# T_STorM32_motor_v251E.net
KiCad netlist of a schematic drawn in EAGLE
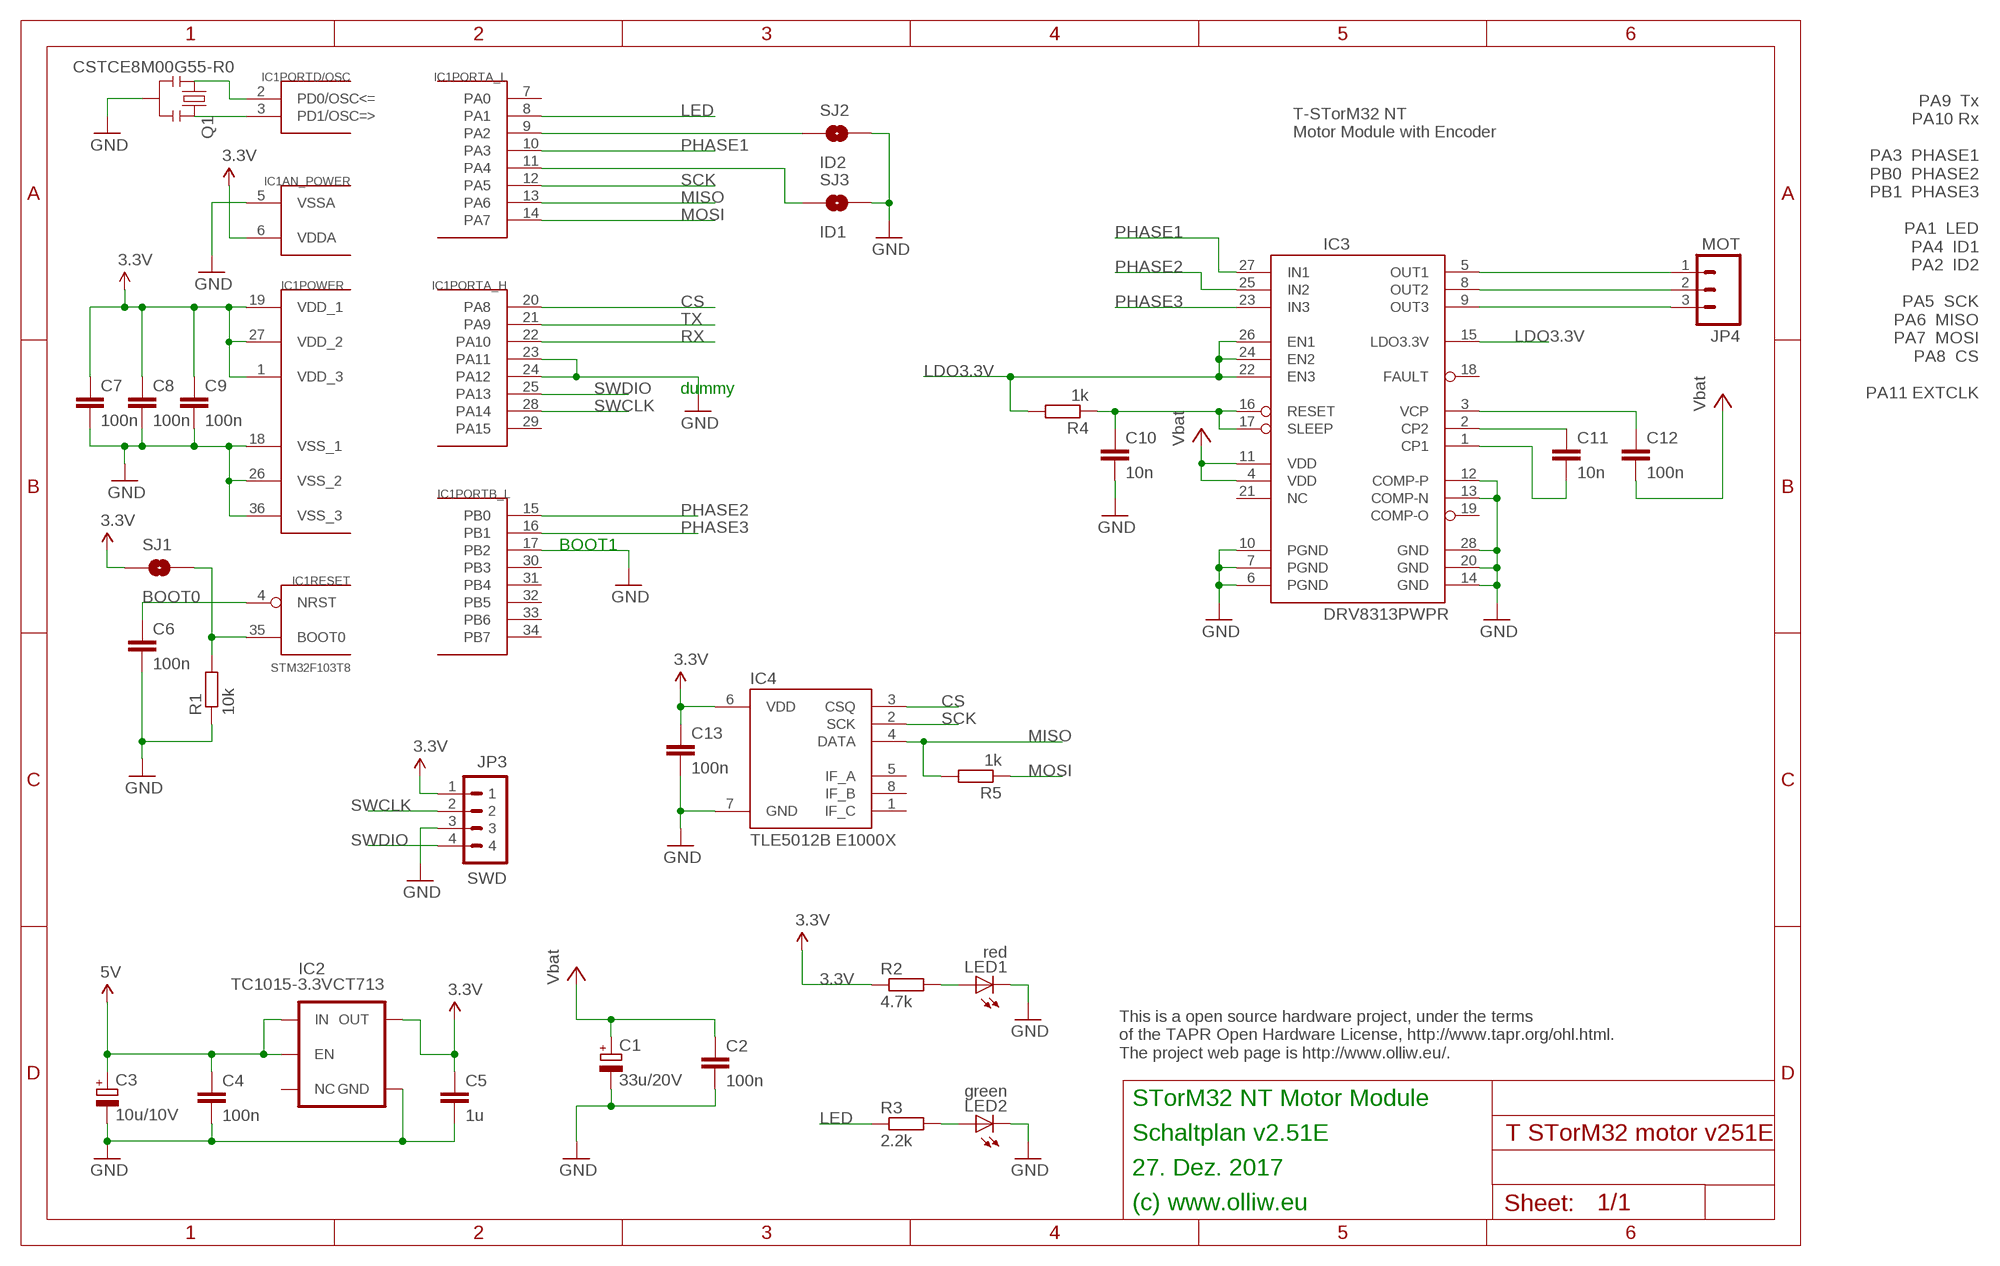
[diagram p0: schematic, sheet 1]

(export (version "E")
  (design (tool "Eeschema 10.0.6"))
  (components
    (comp (ref "C1")
      (value "33u/20V")
      (footprint "eagle-import:SMC_C")
      (libsource (lib "eagle-import") (part "CPOL-EUSMCC"))
    )
    (comp (ref "C2")
      (value "100n")
      (footprint "eagle-import:C0603")
      (libsource (lib "eagle-import") (part "C-EUC0603"))
    )
    (comp (ref "C3")
      (value "10u/10V")
      (footprint "eagle-import:SMC_B")
      (libsource (lib "eagle-import") (part "CPOL-EUSMCB"))
    )
    (comp (ref "C4")
      (value "100n")
      (footprint "eagle-import:C0603")
      (libsource (lib "eagle-import") (part "C-EUC0603"))
    )
    (comp (ref "C5")
      (value "1u")
      (footprint "eagle-import:C0603")
      (libsource (lib "eagle-import") (part "C-EUC0603"))
    )
    (comp (ref "C6")
      (value "100n")
      (footprint "eagle-import:C0603")
      (libsource (lib "eagle-import") (part "C-EUC0603"))
    )
    (comp (ref "C7")
      (value "100n")
      (footprint "eagle-import:C0603")
      (libsource (lib "eagle-import") (part "C-EUC0603"))
    )
    (comp (ref "C8")
      (value "100n")
      (footprint "eagle-import:C0603")
      (libsource (lib "eagle-import") (part "C-EUC0603"))
    )
    (comp (ref "C9")
      (value "100n")
      (footprint "eagle-import:C0603")
      (libsource (lib "eagle-import") (part "C-EUC0603"))
    )
    (comp (ref "C10")
      (value "10n")
      (footprint "eagle-import:C0603")
      (libsource (lib "eagle-import") (part "C-EUC0603"))
    )
    (comp (ref "C11")
      (value "10n")
      (footprint "eagle-import:C0603")
      (libsource (lib "eagle-import") (part "C-EUC0603"))
    )
    (comp (ref "C12")
      (value "100n")
      (footprint "eagle-import:C0603")
      (libsource (lib "eagle-import") (part "C-EUC0603"))
    )
    (comp (ref "C13")
      (value "100n")
      (footprint "eagle-import:C0603")
      (libsource (lib "eagle-import") (part "C-EUC0603"))
    )
    (comp (ref "IC1")
      (value "STM32F103T8")
      (footprint "eagle-import:VFQFPN36")
      (libsource (lib "eagle-import") (part "STM32F10XTXU6"))
    )
    (comp (ref "IC2")
      (value "TC1015-3.3VCT713")
      (footprint "eagle-import:SOT23-5")
      (libsource (lib "eagle-import") (part "V_REG_TPS76433SOT23-5"))
    )
    (comp (ref "IC3")
      (value "DRV8313PWPR")
      (footprint "eagle-import:HTSSOP28")
      (libsource (lib "eagle-import") (part "DRV8313"))
    )
    (comp (ref "IC4")
      (value "TLE5012B E1000X")
      (footprint "eagle-import:SO08")
      (libsource (lib "eagle-import") (part "TLE5012B"))
    )
    (comp (ref "JP3")
      (value "SWD")
      (footprint "eagle-import:4X1_1P27_OCT_BILEX")
      (libsource (lib "eagle-import") (part "P4X1_1P27-OCT_BILEX"))
    )
    (comp (ref "JP4")
      (value "MOT")
      (footprint "eagle-import:1X03_NO_SILK")
      (libsource (lib "eagle-import") (part "M031X03_NO_SILK"))
    )
    (comp (ref "LED1")
      (value "red")
      (footprint "eagle-import:CHIPLED_0603")
      (libsource (lib "eagle-import") (part "LEDCHIPLED_0603"))
    )
    (comp (ref "LED2")
      (value "green")
      (footprint "eagle-import:CHIPLED_0603")
      (libsource (lib "eagle-import") (part "LEDCHIPLED_0603"))
    )
    (comp (ref "Q1")
      (value "CSTCE8M00G55-R0")
      (footprint "eagle-import:RESONATOR-SMD")
      (libsource (lib "eagle-import") (part "RESONATORSMD"))
    )
    (comp (ref "R1")
      (value "10k")
      (footprint "eagle-import:R0603")
      (libsource (lib "eagle-import") (part "R-EU_R0603"))
    )
    (comp (ref "R2")
      (value "4.7k")
      (footprint "eagle-import:R0603")
      (libsource (lib "eagle-import") (part "R-EU_R0603"))
    )
    (comp (ref "R3")
      (value "2.2k")
      (footprint "eagle-import:R0603")
      (libsource (lib "eagle-import") (part "R-EU_R0603"))
    )
    (comp (ref "R4")
      (value "1k")
      (footprint "eagle-import:R0603")
      (libsource (lib "eagle-import") (part "R-EU_R0603"))
    )
    (comp (ref "R5")
      (value "1k")
      (footprint "eagle-import:R0603")
      (libsource (lib "eagle-import") (part "R-EU_R0603"))
    )
    (comp (ref "SJ1")
      (value "BOOT0")
      (footprint "eagle-import:SJ_2S-NO")
      (libsource (lib "eagle-import") (part "SOLDERJUMPERNO"))
    )
    (comp (ref "SJ2")
      (value "ID2")
      (footprint "eagle-import:SJ_2S-NO")
      (libsource (lib "eagle-import") (part "SOLDERJUMPERNO"))
    )
    (comp (ref "SJ3")
      (value "ID1")
      (footprint "eagle-import:SJ_2S-NO")
      (libsource (lib "eagle-import") (part "SOLDERJUMPERNO"))
    )
  )
  (nets
    (net (code "1") (name "/CS") (class "Default")
      (node (ref "IC1") (pin "20") (pinfunction "PA8_20") (pintype "bidirectional"))
      (node (ref "IC4") (pin "3") (pinfunction "CSQ_3") (pintype "input"))
    )
    (net (code "2") (name "/LDO3.3V") (class "Default")
      (node (ref "IC3") (pin "15") (pinfunction "LDO3.3V_15") (pintype "output"))
      (node (ref "IC3") (pin "22") (pinfunction "EN3_22") (pintype "input"))
      (node (ref "IC3") (pin "24") (pinfunction "EN2_24") (pintype "input"))
      (node (ref "IC3") (pin "26") (pinfunction "EN1_26") (pintype "input"))
      (node (ref "R4") (pin "2") (pinfunction "2_2") (pintype "passive"))
    )
    (net (code "3") (name "/LED") (class "Default")
      (node (ref "IC1") (pin "8") (pinfunction "PA1_8") (pintype "bidirectional"))
      (node (ref "R3") (pin "1") (pinfunction "1_1") (pintype "passive"))
    )
    (net (code "4") (name "/MISO") (class "Default")
      (node (ref "IC1") (pin "13") (pinfunction "PA6_13") (pintype "bidirectional"))
      (node (ref "IC4") (pin "4") (pinfunction "DATA_4") (pintype "bidirectional"))
      (node (ref "R5") (pin "2") (pinfunction "2_2") (pintype "passive"))
    )
    (net (code "5") (name "/MOSI") (class "Default")
      (node (ref "IC1") (pin "14") (pinfunction "PA7_14") (pintype "bidirectional"))
      (node (ref "R5") (pin "1") (pinfunction "1_1") (pintype "passive"))
    )
    (net (code "6") (name "/PHASE1") (class "Default")
      (node (ref "IC1") (pin "10") (pinfunction "PA3_10") (pintype "bidirectional"))
      (node (ref "IC3") (pin "27") (pinfunction "IN1_27") (pintype "input"))
    )
    (net (code "7") (name "/PHASE2") (class "Default")
      (node (ref "IC1") (pin "15") (pinfunction "PB0_15") (pintype "bidirectional"))
      (node (ref "IC3") (pin "25") (pinfunction "IN2_25") (pintype "input"))
    )
    (net (code "8") (name "/PHASE3") (class "Default")
      (node (ref "IC1") (pin "16") (pinfunction "PB1_16") (pintype "bidirectional"))
      (node (ref "IC3") (pin "23") (pinfunction "IN3_23") (pintype "input"))
    )
    (net (code "9") (name "/RX") (class "Default")
      (node (ref "IC1") (pin "22") (pinfunction "PA10_22") (pintype "bidirectional"))
    )
    (net (code "10") (name "/SCK") (class "Default")
      (node (ref "IC1") (pin "12") (pinfunction "PA5_12") (pintype "bidirectional"))
      (node (ref "IC4") (pin "2") (pinfunction "SCK_2") (pintype "input"))
    )
    (net (code "11") (name "/SWCLK") (class "Default")
      (node (ref "IC1") (pin "28") (pinfunction "PA14_28") (pintype "bidirectional"))
      (node (ref "JP3") (pin "2") (pinfunction "2_2") (pintype "passive"))
    )
    (net (code "12") (name "/SWDIO") (class "Default")
      (node (ref "IC1") (pin "25") (pinfunction "PA13_25") (pintype "bidirectional"))
      (node (ref "JP3") (pin "4") (pinfunction "4_4") (pintype "passive"))
    )
    (net (code "13") (name "/TX") (class "Default")
      (node (ref "IC1") (pin "21") (pinfunction "PA9_21") (pintype "bidirectional"))
    )
    (net (code "14") (name "3.3V") (class "Default")
      (node (ref "C13") (pin "1") (pinfunction "1_1") (pintype "passive"))
      (node (ref "C5") (pin "1") (pinfunction "1_1") (pintype "passive"))
      (node (ref "C7") (pin "1") (pinfunction "1_1") (pintype "passive"))
      (node (ref "C8") (pin "1") (pinfunction "1_1") (pintype "passive"))
      (node (ref "C9") (pin "1") (pinfunction "1_1") (pintype "passive"))
      (node (ref "IC1") (pin "1") (pinfunction "VDD_3_1") (pintype "power_in"))
      (node (ref "IC1") (pin "19") (pinfunction "VDD_1_19") (pintype "power_in"))
      (node (ref "IC1") (pin "27") (pinfunction "VDD_2_27") (pintype "power_in"))
      (node (ref "IC1") (pin "6") (pinfunction "VDDA_6") (pintype "power_in"))
      (node (ref "IC2") (pin "5") (pinfunction "OUT_5") (pintype "passive"))
      (node (ref "IC4") (pin "6") (pinfunction "VDD_6") (pintype "power_in"))
      (node (ref "JP3") (pin "1") (pinfunction "1_1") (pintype "passive"))
      (node (ref "R2") (pin "1") (pinfunction "1_1") (pintype "passive"))
      (node (ref "SJ1") (pin "1") (pinfunction "1_1") (pintype "passive"))
    )
    (net (code "15") (name "5V") (class "Default")
      (node (ref "C3") (pin "+") (pinfunction "+_+") (pintype "passive"))
      (node (ref "C4") (pin "1") (pinfunction "1_1") (pintype "passive"))
      (node (ref "IC2") (pin "1") (pinfunction "IN_1") (pintype "input"))
      (node (ref "IC2") (pin "3") (pinfunction "EN_3") (pintype "input"))
    )
    (net (code "16") (name "GND") (class "Default")
      (node (ref "C1") (pin "-") (pinfunction "-_-") (pintype "passive"))
      (node (ref "C10") (pin "2") (pinfunction "2_2") (pintype "passive"))
      (node (ref "C13") (pin "2") (pinfunction "2_2") (pintype "passive"))
      (node (ref "C2") (pin "2") (pinfunction "2_2") (pintype "passive"))
      (node (ref "C3") (pin "-") (pinfunction "-_-") (pintype "passive"))
      (node (ref "C4") (pin "2") (pinfunction "2_2") (pintype "passive"))
      (node (ref "C5") (pin "2") (pinfunction "2_2") (pintype "passive"))
      (node (ref "C6") (pin "2") (pinfunction "2_2") (pintype "passive"))
      (node (ref "C7") (pin "2") (pinfunction "2_2") (pintype "passive"))
      (node (ref "C8") (pin "2") (pinfunction "2_2") (pintype "passive"))
      (node (ref "C9") (pin "2") (pinfunction "2_2") (pintype "passive"))
      (node (ref "IC1") (pin "17") (pinfunction "PB2_17") (pintype "bidirectional"))
      (node (ref "IC1") (pin "18") (pinfunction "VSS_1_18") (pintype "power_in"))
      (node (ref "IC1") (pin "23") (pinfunction "PA11_23") (pintype "bidirectional"))
      (node (ref "IC1") (pin "24") (pinfunction "PA12_24") (pintype "bidirectional"))
      (node (ref "IC1") (pin "26") (pinfunction "VSS_2_26") (pintype "power_in"))
      (node (ref "IC1") (pin "36") (pinfunction "VSS_3_36") (pintype "power_in"))
      (node (ref "IC1") (pin "5") (pinfunction "VSSA_5") (pintype "power_in"))
      (node (ref "IC2") (pin "2") (pinfunction "GND_2") (pintype "input"))
      (node (ref "IC3") (pin "10") (pinfunction "PGND_10") (pintype "power_in"))
      (node (ref "IC3") (pin "12") (pinfunction "COMP-P_12") (pintype "input"))
      (node (ref "IC3") (pin "13") (pinfunction "COMP-N_13") (pintype "input"))
      (node (ref "IC3") (pin "14") (pinfunction "GND_14") (pintype "power_in"))
      (node (ref "IC3") (pin "20") (pinfunction "GND_20") (pintype "power_in"))
      (node (ref "IC3") (pin "28") (pinfunction "GND_28") (pintype "power_in"))
      (node (ref "IC3") (pin "6") (pinfunction "PGND_6") (pintype "power_in"))
      (node (ref "IC3") (pin "7") (pinfunction "PGND_7") (pintype "power_in"))
      (node (ref "IC4") (pin "7") (pinfunction "GND_7") (pintype "power_in"))
      (node (ref "JP3") (pin "3") (pinfunction "3_3") (pintype "passive"))
      (node (ref "LED1") (pin "C") (pinfunction "C_C") (pintype "passive"))
      (node (ref "LED2") (pin "C") (pinfunction "C_C") (pintype "passive"))
      (node (ref "Q1") (pin "2") (pinfunction "2_2") (pintype "passive"))
      (node (ref "R1") (pin "1") (pinfunction "1_1") (pintype "passive"))
      (node (ref "SJ2") (pin "2") (pinfunction "2_2") (pintype "passive"))
      (node (ref "SJ3") (pin "2") (pinfunction "2_2") (pintype "passive"))
    )
    (net (code "17") (name "Net-(IC1C-PA2)") (class "Default")
      (node (ref "IC1") (pin "9") (pinfunction "PA2_9") (pintype "bidirectional"))
      (node (ref "SJ2") (pin "1") (pinfunction "1_1") (pintype "passive"))
    )
    (net (code "18") (name "Net-(IC1C-PA4)") (class "Default")
      (node (ref "IC1") (pin "11") (pinfunction "PA4_11") (pintype "bidirectional"))
      (node (ref "SJ3") (pin "1") (pinfunction "1_1") (pintype "passive"))
    )
    (net (code "19") (name "Net-(IC1E-PD0{slash}OSC<=)") (class "Default")
      (node (ref "IC1") (pin "2") (pinfunction "PD0/OSC<=_2") (pintype "bidirectional"))
      (node (ref "Q1") (pin "1") (pinfunction "1_1") (pintype "passive"))
    )
    (net (code "20") (name "Net-(IC1E-PD1{slash}OSC=>)") (class "Default")
      (node (ref "IC1") (pin "3") (pinfunction "PD1/OSC=>_3") (pintype "bidirectional"))
      (node (ref "Q1") (pin "3") (pinfunction "3_3") (pintype "passive"))
    )
    (net (code "21") (name "Net-(IC1G-BOOT0)") (class "Default")
      (node (ref "IC1") (pin "35") (pinfunction "BOOT0_35") (pintype "input"))
      (node (ref "R1") (pin "2") (pinfunction "2_2") (pintype "passive"))
      (node (ref "SJ1") (pin "2") (pinfunction "2_2") (pintype "passive"))
    )
    (net (code "22") (name "Net-(IC1G-NRST)") (class "Default")
      (node (ref "C6") (pin "1") (pinfunction "1_1") (pintype "passive"))
      (node (ref "IC1") (pin "4") (pinfunction "NRST_4") (pintype "input"))
    )
    (net (code "23") (name "Net-(IC3-CP1)") (class "Default")
      (node (ref "C11") (pin "2") (pinfunction "2_2") (pintype "passive"))
      (node (ref "IC3") (pin "1") (pinfunction "CP1_1") (pintype "bidirectional"))
    )
    (net (code "24") (name "Net-(IC3-CP2)") (class "Default")
      (node (ref "C11") (pin "1") (pinfunction "1_1") (pintype "passive"))
      (node (ref "IC3") (pin "2") (pinfunction "CP2_2") (pintype "bidirectional"))
    )
    (net (code "25") (name "Net-(IC3-OUT1)") (class "Default")
      (node (ref "IC3") (pin "5") (pinfunction "OUT1_5") (pintype "output"))
      (node (ref "JP4") (pin "1") (pinfunction "1_1") (pintype "passive"))
    )
    (net (code "26") (name "Net-(IC3-OUT2)") (class "Default")
      (node (ref "IC3") (pin "8") (pinfunction "OUT2_8") (pintype "output"))
      (node (ref "JP4") (pin "2") (pinfunction "2_2") (pintype "passive"))
    )
    (net (code "27") (name "Net-(IC3-OUT3)") (class "Default")
      (node (ref "IC3") (pin "9") (pinfunction "OUT3_9") (pintype "output"))
      (node (ref "JP4") (pin "3") (pinfunction "3_3") (pintype "passive"))
    )
    (net (code "28") (name "Net-(IC3-RESET)") (class "Default")
      (node (ref "C10") (pin "1") (pinfunction "1_1") (pintype "passive"))
      (node (ref "IC3") (pin "16") (pinfunction "RESET_16") (pintype "input"))
      (node (ref "IC3") (pin "17") (pinfunction "SLEEP_17") (pintype "input"))
      (node (ref "R4") (pin "1") (pinfunction "1_1") (pintype "passive"))
    )
    (net (code "29") (name "Net-(IC3-VCP)") (class "Default")
      (node (ref "C12") (pin "1") (pinfunction "1_1") (pintype "passive"))
      (node (ref "IC3") (pin "3") (pinfunction "VCP_3") (pintype "bidirectional"))
    )
    (net (code "30") (name "Net-(LED1-PadA)") (class "Default")
      (node (ref "LED1") (pin "A") (pinfunction "A_A") (pintype "passive"))
      (node (ref "R2") (pin "2") (pinfunction "2_2") (pintype "passive"))
    )
    (net (code "31") (name "Net-(LED2-PadA)") (class "Default")
      (node (ref "LED2") (pin "A") (pinfunction "A_A") (pintype "passive"))
      (node (ref "R3") (pin "2") (pinfunction "2_2") (pintype "passive"))
    )
    (net (code "32") (name "Vbat") (class "Default")
      (node (ref "C1") (pin "+") (pinfunction "+_+") (pintype "passive"))
      (node (ref "C12") (pin "2") (pinfunction "2_2") (pintype "passive"))
      (node (ref "C2") (pin "1") (pinfunction "1_1") (pintype "passive"))
      (node (ref "IC3") (pin "11") (pinfunction "VDD_11") (pintype "power_in"))
      (node (ref "IC3") (pin "4") (pinfunction "VDD_4") (pintype "power_in"))
    )
    (net (code "33") (name "unconnected-(IC1B-PA15-Pad29)") (class "Default")
      (node (ref "IC1") (pin "29") (pinfunction "PA15_29") (pintype "bidirectional"))
    )
    (net (code "34") (name "unconnected-(IC1C-PA0-Pad7)") (class "Default")
      (node (ref "IC1") (pin "7") (pinfunction "PA0_7") (pintype "bidirectional"))
    )
    (net (code "35") (name "unconnected-(IC1D-PB3-Pad30)") (class "Default")
      (node (ref "IC1") (pin "30") (pinfunction "PB3_30") (pintype "bidirectional"))
    )
    (net (code "36") (name "unconnected-(IC1D-PB4-Pad31)") (class "Default")
      (node (ref "IC1") (pin "31") (pinfunction "PB4_31") (pintype "bidirectional"))
    )
    (net (code "37") (name "unconnected-(IC1D-PB5-Pad32)") (class "Default")
      (node (ref "IC1") (pin "32") (pinfunction "PB5_32") (pintype "bidirectional"))
    )
    (net (code "38") (name "unconnected-(IC1D-PB6-Pad33)") (class "Default")
      (node (ref "IC1") (pin "33") (pinfunction "PB6_33") (pintype "bidirectional"))
    )
    (net (code "39") (name "unconnected-(IC1D-PB7-Pad34)") (class "Default")
      (node (ref "IC1") (pin "34") (pinfunction "PB7_34") (pintype "bidirectional"))
    )
    (net (code "40") (name "unconnected-(IC2-NC-Pad4)") (class "Default")
      (node (ref "IC2") (pin "4") (pinfunction "NC_4") (pintype "input"))
    )
    (net (code "41") (name "unconnected-(IC3-COMP-O-Pad19)") (class "Default")
      (node (ref "IC3") (pin "19") (pinfunction "COMP-O_19") (pintype "output"))
    )
    (net (code "42") (name "unconnected-(IC3-FAULT-Pad18)") (class "Default")
      (node (ref "IC3") (pin "18") (pinfunction "FAULT_18") (pintype "output"))
    )
    (net (code "43") (name "unconnected-(IC3-NC-Pad21)") (class "Default")
      (node (ref "IC3") (pin "21") (pinfunction "NC_21") (pintype "no_connect"))
    )
    (net (code "44") (name "unconnected-(IC4-IF_A-Pad5)") (class "Default")
      (node (ref "IC4") (pin "5") (pinfunction "IF_A_5") (pintype "bidirectional"))
    )
    (net (code "45") (name "unconnected-(IC4-IF_B-Pad8)") (class "Default")
      (node (ref "IC4") (pin "8") (pinfunction "IF_B_8") (pintype "output"))
    )
    (net (code "46") (name "unconnected-(IC4-IF_C-Pad1)") (class "Default")
      (node (ref "IC4") (pin "1") (pinfunction "IF_C_1") (pintype "bidirectional"))
    )
  )
)
